# out.net
KiCad netlist of a schematic drawn in EAGLE
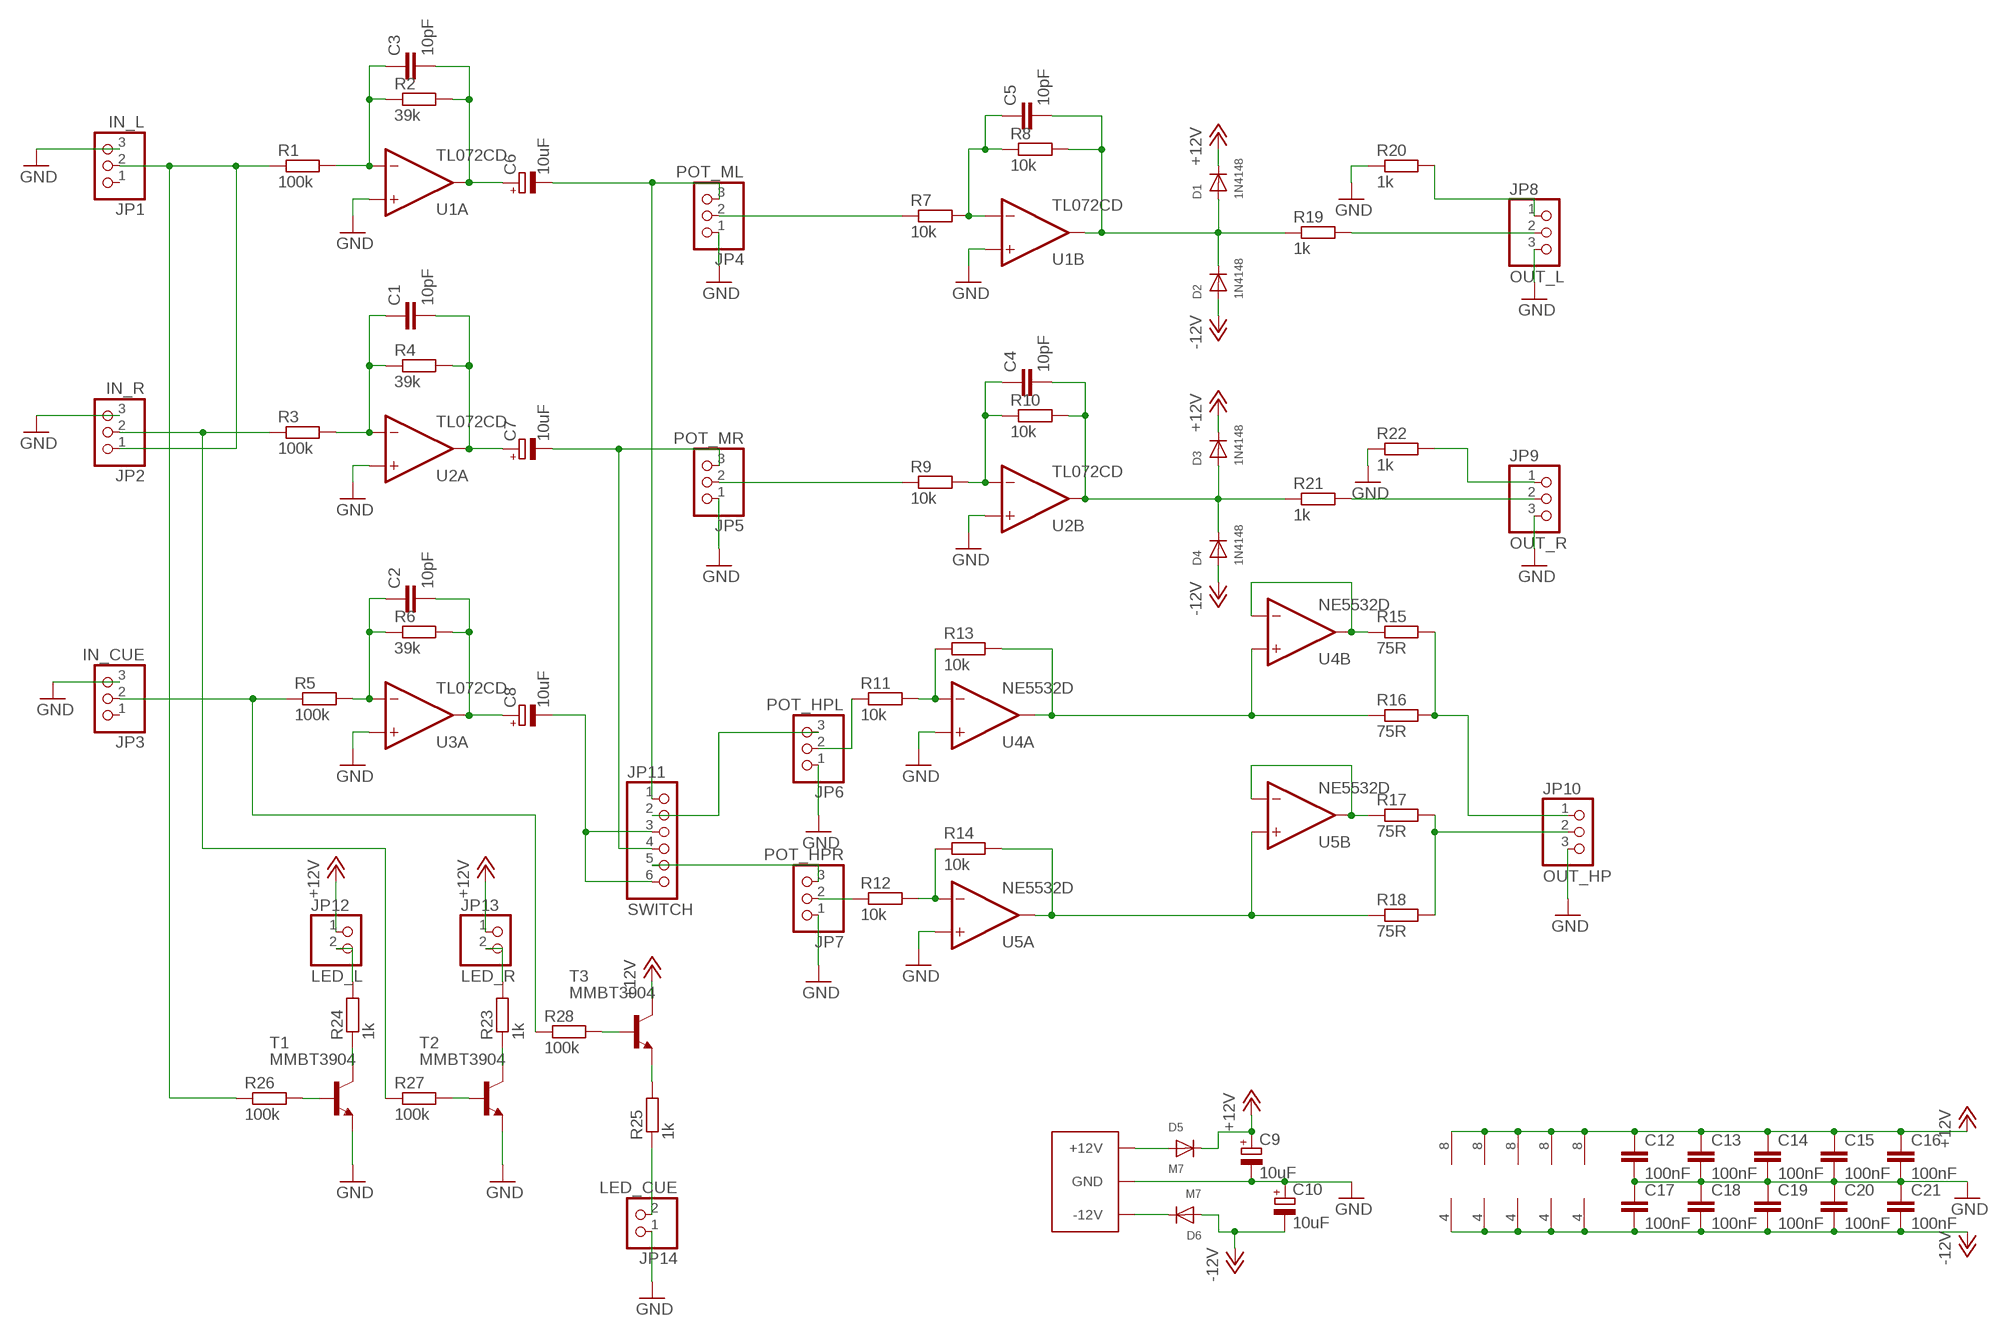
[diagram p0: schematic, sheet 1]

(export (version "E")
  (design (tool "Eeschema 10.0.6"))
  (components
    (comp (ref "C1")
      (value "10pF")
      (footprint "eagle-import:C0402")
      (libsource (lib "eagle-import") (part "C-EUC0402"))
    )
    (comp (ref "C2")
      (value "10pF")
      (footprint "eagle-import:C0402")
      (libsource (lib "eagle-import") (part "C-EUC0402"))
    )
    (comp (ref "C3")
      (value "10pF")
      (footprint "eagle-import:C0402")
      (libsource (lib "eagle-import") (part "C-EUC0402"))
    )
    (comp (ref "C4")
      (value "10pF")
      (footprint "eagle-import:C0402")
      (libsource (lib "eagle-import") (part "C-EUC0402"))
    )
    (comp (ref "C5")
      (value "10pF")
      (footprint "eagle-import:C0402")
      (libsource (lib "eagle-import") (part "C-EUC0402"))
    )
    (comp (ref "C6")
      (value "10uF")
      (footprint "eagle-import:A_3216-18W")
      (libsource (lib "eagle-import") (part "CPOL-EUA/3216-18W"))
    )
    (comp (ref "C7")
      (value "10uF")
      (footprint "eagle-import:A_3216-18W")
      (libsource (lib "eagle-import") (part "CPOL-EUA/3216-18W"))
    )
    (comp (ref "C8")
      (value "10uF")
      (footprint "eagle-import:A_3216-18W")
      (libsource (lib "eagle-import") (part "CPOL-EUA/3216-18W"))
    )
    (comp (ref "C9")
      (value "10uF")
      (footprint "eagle-import:A_3216-18W")
      (libsource (lib "eagle-import") (part "CPOL-EUA/3216-18W"))
    )
    (comp (ref "C10")
      (value "10uF")
      (footprint "eagle-import:A_3216-18W")
      (libsource (lib "eagle-import") (part "CPOL-EUA/3216-18W"))
    )
    (comp (ref "C11")
      (value "EURO_POWER_LOCKFAT-LOCK")
      (footprint "eagle-import:EURO_PWR_HEADER_LOCK")
      (libsource (lib "eagle-import") (part "EURO_POWER_LOCKFAT-LOCK"))
    )
    (comp (ref "C12")
      (value "100nF")
      (footprint "eagle-import:C0402")
      (libsource (lib "eagle-import") (part "C-EUC0402"))
    )
    (comp (ref "C13")
      (value "100nF")
      (footprint "eagle-import:C0402")
      (libsource (lib "eagle-import") (part "C-EUC0402"))
    )
    (comp (ref "C14")
      (value "100nF")
      (footprint "eagle-import:C0402")
      (libsource (lib "eagle-import") (part "C-EUC0402"))
    )
    (comp (ref "C15")
      (value "100nF")
      (footprint "eagle-import:C0402")
      (libsource (lib "eagle-import") (part "C-EUC0402"))
    )
    (comp (ref "C16")
      (value "100nF")
      (footprint "eagle-import:C0402")
      (libsource (lib "eagle-import") (part "C-EUC0402"))
    )
    (comp (ref "C17")
      (value "100nF")
      (footprint "eagle-import:C0402")
      (libsource (lib "eagle-import") (part "C-EUC0402"))
    )
    (comp (ref "C18")
      (value "100nF")
      (footprint "eagle-import:C0402")
      (libsource (lib "eagle-import") (part "C-EUC0402"))
    )
    (comp (ref "C19")
      (value "100nF")
      (footprint "eagle-import:C0402")
      (libsource (lib "eagle-import") (part "C-EUC0402"))
    )
    (comp (ref "C20")
      (value "100nF")
      (footprint "eagle-import:C0402")
      (libsource (lib "eagle-import") (part "C-EUC0402"))
    )
    (comp (ref "C21")
      (value "100nF")
      (footprint "eagle-import:C0402")
      (libsource (lib "eagle-import") (part "C-EUC0402"))
    )
    (comp (ref "D1")
      (value "1N4148")
      (footprint "eagle-import:SOD-323F")
      (libsource (lib "eagle-import") (part "DIODESOD-323F"))
    )
    (comp (ref "D2")
      (value "1N4148")
      (footprint "eagle-import:SOD-323F")
      (libsource (lib "eagle-import") (part "DIODESOD-323F"))
    )
    (comp (ref "D3")
      (value "1N4148")
      (footprint "eagle-import:SOD-323F")
      (libsource (lib "eagle-import") (part "DIODESOD-323F"))
    )
    (comp (ref "D4")
      (value "1N4148")
      (footprint "eagle-import:SOD-323F")
      (libsource (lib "eagle-import") (part "DIODESOD-323F"))
    )
    (comp (ref "D5")
      (value "M7")
      (footprint "eagle-import:SMADIODE")
      (libsource (lib "eagle-import") (part "DIODESMA"))
    )
    (comp (ref "D6")
      (value "M7")
      (footprint "eagle-import:SMADIODE")
      (libsource (lib "eagle-import") (part "DIODESMA"))
    )
    (comp (ref "JP1")
      (value "IN_L")
      (footprint "eagle-import:1X03")
      (libsource (lib "eagle-import") (part "PINHD-1X3"))
    )
    (comp (ref "JP2")
      (value "IN_R")
      (footprint "eagle-import:1X03")
      (libsource (lib "eagle-import") (part "PINHD-1X3"))
    )
    (comp (ref "JP3")
      (value "IN_CUE")
      (footprint "eagle-import:1X03")
      (libsource (lib "eagle-import") (part "PINHD-1X3"))
    )
    (comp (ref "JP4")
      (value "POT_ML")
      (footprint "eagle-import:1X03")
      (libsource (lib "eagle-import") (part "PINHD-1X3"))
    )
    (comp (ref "JP5")
      (value "POT_MR")
      (footprint "eagle-import:1X03")
      (libsource (lib "eagle-import") (part "PINHD-1X3"))
    )
    (comp (ref "JP6")
      (value "POT_HPL")
      (footprint "eagle-import:1X03")
      (libsource (lib "eagle-import") (part "PINHD-1X3"))
    )
    (comp (ref "JP7")
      (value "POT_HPR")
      (footprint "eagle-import:1X03")
      (libsource (lib "eagle-import") (part "PINHD-1X3"))
    )
    (comp (ref "JP8")
      (value "OUT_L")
      (footprint "eagle-import:1X03")
      (libsource (lib "eagle-import") (part "PINHD-1X3"))
    )
    (comp (ref "JP9")
      (value "OUT_R")
      (footprint "eagle-import:1X03")
      (libsource (lib "eagle-import") (part "PINHD-1X3"))
    )
    (comp (ref "JP10")
      (value "OUT_HP")
      (footprint "eagle-import:1X03")
      (libsource (lib "eagle-import") (part "PINHD-1X3"))
    )
    (comp (ref "JP11")
      (value "SWITCH")
      (footprint "eagle-import:1X06")
      (libsource (lib "eagle-import") (part "PINHD-1X6"))
    )
    (comp (ref "JP12")
      (value "LED_L")
      (footprint "eagle-import:1X02")
      (libsource (lib "eagle-import") (part "PINHD-1X2"))
    )
    (comp (ref "JP13")
      (value "LED_R")
      (footprint "eagle-import:1X02")
      (libsource (lib "eagle-import") (part "PINHD-1X2"))
    )
    (comp (ref "JP14")
      (value "LED_CUE")
      (footprint "eagle-import:1X02")
      (libsource (lib "eagle-import") (part "PINHD-1X2"))
    )
    (comp (ref "R1")
      (value "100k")
      (footprint "eagle-import:R0402")
      (libsource (lib "eagle-import") (part "R-EU_R0402"))
    )
    (comp (ref "R2")
      (value "39k")
      (footprint "eagle-import:R0402")
      (libsource (lib "eagle-import") (part "R-EU_R0402"))
    )
    (comp (ref "R3")
      (value "100k")
      (footprint "eagle-import:R0402")
      (libsource (lib "eagle-import") (part "R-EU_R0402"))
    )
    (comp (ref "R4")
      (value "39k")
      (footprint "eagle-import:R0402")
      (libsource (lib "eagle-import") (part "R-EU_R0402"))
    )
    (comp (ref "R5")
      (value "100k")
      (footprint "eagle-import:R0402")
      (libsource (lib "eagle-import") (part "R-EU_R0402"))
    )
    (comp (ref "R6")
      (value "39k")
      (footprint "eagle-import:R0402")
      (libsource (lib "eagle-import") (part "R-EU_R0402"))
    )
    (comp (ref "R7")
      (value "10k")
      (footprint "eagle-import:R0402")
      (libsource (lib "eagle-import") (part "R-EU_R0402"))
    )
    (comp (ref "R8")
      (value "10k")
      (footprint "eagle-import:R0402")
      (libsource (lib "eagle-import") (part "R-EU_R0402"))
    )
    (comp (ref "R9")
      (value "10k")
      (footprint "eagle-import:R0402")
      (libsource (lib "eagle-import") (part "R-EU_R0402"))
    )
    (comp (ref "R10")
      (value "10k")
      (footprint "eagle-import:R0402")
      (libsource (lib "eagle-import") (part "R-EU_R0402"))
    )
    (comp (ref "R11")
      (value "10k")
      (footprint "eagle-import:R0402")
      (libsource (lib "eagle-import") (part "R-EU_R0402"))
    )
    (comp (ref "R12")
      (value "10k")
      (footprint "eagle-import:R0402")
      (libsource (lib "eagle-import") (part "R-EU_R0402"))
    )
    (comp (ref "R13")
      (value "10k")
      (footprint "eagle-import:R0402")
      (libsource (lib "eagle-import") (part "R-EU_R0402"))
    )
    (comp (ref "R14")
      (value "10k")
      (footprint "eagle-import:R0402")
      (libsource (lib "eagle-import") (part "R-EU_R0402"))
    )
    (comp (ref "R15")
      (value "75R")
      (footprint "eagle-import:R0402")
      (libsource (lib "eagle-import") (part "R-EU_R0402"))
    )
    (comp (ref "R16")
      (value "75R")
      (footprint "eagle-import:R0402")
      (libsource (lib "eagle-import") (part "R-EU_R0402"))
    )
    (comp (ref "R17")
      (value "75R")
      (footprint "eagle-import:R0402")
      (libsource (lib "eagle-import") (part "R-EU_R0402"))
    )
    (comp (ref "R18")
      (value "75R")
      (footprint "eagle-import:R0402")
      (libsource (lib "eagle-import") (part "R-EU_R0402"))
    )
    (comp (ref "R19")
      (value "1k")
      (footprint "eagle-import:R0402")
      (libsource (lib "eagle-import") (part "R-EU_R0402"))
    )
    (comp (ref "R20")
      (value "1k")
      (footprint "eagle-import:R0402")
      (libsource (lib "eagle-import") (part "R-EU_R0402"))
    )
    (comp (ref "R21")
      (value "1k")
      (footprint "eagle-import:R0402")
      (libsource (lib "eagle-import") (part "R-EU_R0402"))
    )
    (comp (ref "R22")
      (value "1k")
      (footprint "eagle-import:R0402")
      (libsource (lib "eagle-import") (part "R-EU_R0402"))
    )
    (comp (ref "R23")
      (value "1k")
      (footprint "eagle-import:R0402")
      (libsource (lib "eagle-import") (part "R-EU_R0402"))
    )
    (comp (ref "R24")
      (value "1k")
      (footprint "eagle-import:R0402")
      (libsource (lib "eagle-import") (part "R-EU_R0402"))
    )
    (comp (ref "R25")
      (value "1k")
      (footprint "eagle-import:R0402")
      (libsource (lib "eagle-import") (part "R-EU_R0402"))
    )
    (comp (ref "R26")
      (value "100k")
      (footprint "eagle-import:R0402")
      (libsource (lib "eagle-import") (part "R-EU_R0402"))
    )
    (comp (ref "R27")
      (value "100k")
      (footprint "eagle-import:R0402")
      (libsource (lib "eagle-import") (part "R-EU_R0402"))
    )
    (comp (ref "R28")
      (value "100k")
      (footprint "eagle-import:R0402")
      (libsource (lib "eagle-import") (part "R-EU_R0402"))
    )
    (comp (ref "T1")
      (value "MMBT3904")
      (footprint "eagle-import:SOT23-BEC")
      (libsource (lib "eagle-import") (part "-NPN-SOT23-BECMMBT3904LT1"))
    )
    (comp (ref "T2")
      (value "MMBT3904")
      (footprint "eagle-import:SOT23-BEC")
      (libsource (lib "eagle-import") (part "-NPN-SOT23-BECMMBT3904LT1"))
    )
    (comp (ref "T3")
      (value "MMBT3904")
      (footprint "eagle-import:SOT23-BEC")
      (libsource (lib "eagle-import") (part "-NPN-SOT23-BECMMBT3904LT1"))
    )
    (comp (ref "U1")
      (value "TL072CD")
      (footprint "eagle-import:SOIC8")
      (libsource (lib "eagle-import") (part "TL072DC"))
    )
    (comp (ref "U2")
      (value "TL072CD")
      (footprint "eagle-import:SOIC8")
      (libsource (lib "eagle-import") (part "TL072DC"))
    )
    (comp (ref "U3")
      (value "TL072CD")
      (footprint "eagle-import:SOIC8")
      (libsource (lib "eagle-import") (part "TL072DC"))
    )
    (comp (ref "U4")
      (value "NE5532D")
      (footprint "eagle-import:SOIC8")
      (libsource (lib "eagle-import") (part "NE5532D"))
    )
    (comp (ref "U5")
      (value "NE5532D")
      (footprint "eagle-import:SOIC8")
      (libsource (lib "eagle-import") (part "NE5532D"))
    )
  )
  (nets
    (net (code "1") (name "+12V") (class "Default")
      (node (ref "C12") (pin "1") (pinfunction "1_1") (pintype "passive"))
      (node (ref "C13") (pin "1") (pinfunction "1_1") (pintype "passive"))
      (node (ref "C14") (pin "1") (pinfunction "1_1") (pintype "passive"))
      (node (ref "C15") (pin "1") (pinfunction "1_1") (pintype "passive"))
      (node (ref "C16") (pin "1") (pinfunction "1_1") (pintype "passive"))
      (node (ref "C9") (pin "+") (pinfunction "+_+") (pintype "passive"))
      (node (ref "D1") (pin "C") (pinfunction "C_C") (pintype "passive"))
      (node (ref "D3") (pin "C") (pinfunction "C_C") (pintype "passive"))
      (node (ref "D5") (pin "C") (pinfunction "C_C") (pintype "passive"))
      (node (ref "JP12") (pin "1") (pinfunction "1_1") (pintype "passive"))
      (node (ref "JP13") (pin "1") (pinfunction "1_1") (pintype "passive"))
      (node (ref "T3") (pin "C") (pinfunction "C_C") (pintype "passive"))
      (node (ref "U1") (pin "8") (pinfunction "V+_8") (pintype "power_in"))
      (node (ref "U2") (pin "8") (pinfunction "V+_8") (pintype "power_in"))
      (node (ref "U3") (pin "8") (pinfunction "V+_8") (pintype "power_in"))
      (node (ref "U4") (pin "8") (pinfunction "V+_8") (pintype "power_in"))
      (node (ref "U5") (pin "8") (pinfunction "V+_8") (pintype "power_in"))
    )
    (net (code "2") (name "-12V") (class "Default")
      (node (ref "C10") (pin "-") (pinfunction "-_-") (pintype "passive"))
      (node (ref "C17") (pin "2") (pinfunction "2_2") (pintype "passive"))
      (node (ref "C18") (pin "2") (pinfunction "2_2") (pintype "passive"))
      (node (ref "C19") (pin "2") (pinfunction "2_2") (pintype "passive"))
      (node (ref "C20") (pin "2") (pinfunction "2_2") (pintype "passive"))
      (node (ref "C21") (pin "2") (pinfunction "2_2") (pintype "passive"))
      (node (ref "D2") (pin "A") (pinfunction "A_A") (pintype "passive"))
      (node (ref "D4") (pin "A") (pinfunction "A_A") (pintype "passive"))
      (node (ref "D6") (pin "A") (pinfunction "A_A") (pintype "passive"))
      (node (ref "U1") (pin "4") (pinfunction "V-_4") (pintype "power_in"))
      (node (ref "U2") (pin "4") (pinfunction "V-_4") (pintype "power_in"))
      (node (ref "U3") (pin "4") (pinfunction "V-_4") (pintype "power_in"))
      (node (ref "U4") (pin "4") (pinfunction "V-_4") (pintype "power_in"))
      (node (ref "U5") (pin "4") (pinfunction "V-_4") (pintype "power_in"))
    )
    (net (code "3") (name "GND") (class "Default")
      (node (ref "C10") (pin "+") (pinfunction "+_+") (pintype "passive"))
      (node (ref "C11") (pin "GND1") (pinfunction "GND_GND1") (pintype "bidirectional"))
      (node (ref "C11") (pin "GND2") (pinfunction "GND_GND2") (pintype "bidirectional"))
      (node (ref "C11") (pin "GND3") (pinfunction "GND_GND3") (pintype "bidirectional"))
      (node (ref "C11") (pin "GND4") (pinfunction "GND_GND4") (pintype "bidirectional"))
      (node (ref "C11") (pin "GND5") (pinfunction "GND_GND5") (pintype "bidirectional"))
      (node (ref "C11") (pin "GND6") (pinfunction "GND_GND6") (pintype "bidirectional"))
      (node (ref "C12") (pin "2") (pinfunction "2_2") (pintype "passive"))
      (node (ref "C13") (pin "2") (pinfunction "2_2") (pintype "passive"))
      (node (ref "C14") (pin "2") (pinfunction "2_2") (pintype "passive"))
      (node (ref "C15") (pin "2") (pinfunction "2_2") (pintype "passive"))
      (node (ref "C16") (pin "2") (pinfunction "2_2") (pintype "passive"))
      (node (ref "C17") (pin "1") (pinfunction "1_1") (pintype "passive"))
      (node (ref "C18") (pin "1") (pinfunction "1_1") (pintype "passive"))
      (node (ref "C19") (pin "1") (pinfunction "1_1") (pintype "passive"))
      (node (ref "C20") (pin "1") (pinfunction "1_1") (pintype "passive"))
      (node (ref "C21") (pin "1") (pinfunction "1_1") (pintype "passive"))
      (node (ref "C9") (pin "-") (pinfunction "-_-") (pintype "passive"))
      (node (ref "JP1") (pin "3") (pinfunction "3_3") (pintype "passive"))
      (node (ref "JP10") (pin "3") (pinfunction "3_3") (pintype "passive"))
      (node (ref "JP14") (pin "1") (pinfunction "1_1") (pintype "passive"))
      (node (ref "JP2") (pin "3") (pinfunction "3_3") (pintype "passive"))
      (node (ref "JP3") (pin "3") (pinfunction "3_3") (pintype "passive"))
      (node (ref "JP4") (pin "1") (pinfunction "1_1") (pintype "passive"))
      (node (ref "JP5") (pin "1") (pinfunction "1_1") (pintype "passive"))
      (node (ref "JP6") (pin "1") (pinfunction "1_1") (pintype "passive"))
      (node (ref "JP7") (pin "1") (pinfunction "1_1") (pintype "passive"))
      (node (ref "JP8") (pin "3") (pinfunction "3_3") (pintype "passive"))
      (node (ref "JP9") (pin "3") (pinfunction "3_3") (pintype "passive"))
      (node (ref "R20") (pin "1") (pinfunction "1_1") (pintype "passive"))
      (node (ref "R22") (pin "1") (pinfunction "1_1") (pintype "passive"))
      (node (ref "T1") (pin "E") (pinfunction "E_E") (pintype "passive"))
      (node (ref "T2") (pin "E") (pinfunction "E_E") (pintype "passive"))
      (node (ref "U1") (pin "3") (pinfunction "+IN_3") (pintype "input"))
      (node (ref "U1") (pin "5") (pinfunction "+IN_5") (pintype "input"))
      (node (ref "U2") (pin "3") (pinfunction "+IN_3") (pintype "input"))
      (node (ref "U2") (pin "5") (pinfunction "+IN_5") (pintype "input"))
      (node (ref "U3") (pin "3") (pinfunction "+IN_3") (pintype "input"))
      (node (ref "U4") (pin "3") (pinfunction "+IN_3") (pintype "input"))
      (node (ref "U5") (pin "3") (pinfunction "+IN_3") (pintype "input"))
    )
    (net (code "4") (name "Net-(C6-Pad-)") (class "Default")
      (node (ref "C6") (pin "-") (pinfunction "-_-") (pintype "passive"))
      (node (ref "JP11") (pin "1") (pinfunction "1_1") (pintype "passive"))
      (node (ref "JP4") (pin "3") (pinfunction "3_3") (pintype "passive"))
    )
    (net (code "5") (name "Net-(C7-Pad-)") (class "Default")
      (node (ref "C7") (pin "-") (pinfunction "-_-") (pintype "passive"))
      (node (ref "JP11") (pin "4") (pinfunction "4_4") (pintype "passive"))
      (node (ref "JP5") (pin "3") (pinfunction "3_3") (pintype "passive"))
    )
    (net (code "6") (name "Net-(C8-Pad-)") (class "Default")
      (node (ref "C8") (pin "-") (pinfunction "-_-") (pintype "passive"))
      (node (ref "JP11") (pin "3") (pinfunction "3_3") (pintype "passive"))
      (node (ref "JP11") (pin "6") (pinfunction "6_6") (pintype "passive"))
    )
    (net (code "7") (name "Net-(C11-+12V-PadPOS1)") (class "Default")
      (node (ref "C11") (pin "POS1") (pinfunction "+12V_POS1") (pintype "bidirectional"))
      (node (ref "C11") (pin "POS2") (pinfunction "+12V_POS2") (pintype "bidirectional"))
      (node (ref "D5") (pin "A") (pinfunction "A_A") (pintype "passive"))
    )
    (net (code "8") (name "Net-(C11--12V-PadNEG1)") (class "Default")
      (node (ref "C11") (pin "NEG1") (pinfunction "-12V_NEG1") (pintype "bidirectional"))
      (node (ref "C11") (pin "NEG2") (pinfunction "-12V_NEG2") (pintype "bidirectional"))
      (node (ref "D6") (pin "C") (pinfunction "C_C") (pintype "passive"))
    )
    (net (code "9") (name "Net-(JP1-Pad2)") (class "Default")
      (node (ref "JP1") (pin "2") (pinfunction "2_2") (pintype "passive"))
      (node (ref "JP2") (pin "1") (pinfunction "1_1") (pintype "passive"))
      (node (ref "R1") (pin "1") (pinfunction "1_1") (pintype "passive"))
      (node (ref "R26") (pin "1") (pinfunction "1_1") (pintype "passive"))
    )
    (net (code "10") (name "Net-(JP2-Pad2)") (class "Default")
      (node (ref "JP2") (pin "2") (pinfunction "2_2") (pintype "passive"))
      (node (ref "R27") (pin "1") (pinfunction "1_1") (pintype "passive"))
      (node (ref "R3") (pin "1") (pinfunction "1_1") (pintype "passive"))
    )
    (net (code "11") (name "Net-(JP3-Pad2)") (class "Default")
      (node (ref "JP3") (pin "2") (pinfunction "2_2") (pintype "passive"))
      (node (ref "R28") (pin "1") (pinfunction "1_1") (pintype "passive"))
      (node (ref "R5") (pin "1") (pinfunction "1_1") (pintype "passive"))
    )
    (net (code "12") (name "Net-(JP4-Pad2)") (class "Default")
      (node (ref "JP4") (pin "2") (pinfunction "2_2") (pintype "passive"))
      (node (ref "R7") (pin "1") (pinfunction "1_1") (pintype "passive"))
    )
    (net (code "13") (name "Net-(JP5-Pad2)") (class "Default")
      (node (ref "JP5") (pin "2") (pinfunction "2_2") (pintype "passive"))
      (node (ref "R9") (pin "1") (pinfunction "1_1") (pintype "passive"))
    )
    (net (code "14") (name "Net-(JP6-Pad2)") (class "Default")
      (node (ref "JP6") (pin "2") (pinfunction "2_2") (pintype "passive"))
      (node (ref "R11") (pin "1") (pinfunction "1_1") (pintype "passive"))
    )
    (net (code "15") (name "Net-(JP7-Pad2)") (class "Default")
      (node (ref "JP7") (pin "2") (pinfunction "2_2") (pintype "passive"))
      (node (ref "R12") (pin "1") (pinfunction "1_1") (pintype "passive"))
    )
    (net (code "16") (name "Net-(JP8-Pad1)") (class "Default")
      (node (ref "JP8") (pin "1") (pinfunction "1_1") (pintype "passive"))
      (node (ref "R20") (pin "2") (pinfunction "2_2") (pintype "passive"))
    )
    (net (code "17") (name "Net-(JP8-Pad2)") (class "Default")
      (node (ref "JP8") (pin "2") (pinfunction "2_2") (pintype "passive"))
      (node (ref "R19") (pin "2") (pinfunction "2_2") (pintype "passive"))
    )
    (net (code "18") (name "Net-(JP9-Pad1)") (class "Default")
      (node (ref "JP9") (pin "1") (pinfunction "1_1") (pintype "passive"))
      (node (ref "R22") (pin "2") (pinfunction "2_2") (pintype "passive"))
    )
    (net (code "19") (name "Net-(JP9-Pad2)") (class "Default")
      (node (ref "JP9") (pin "2") (pinfunction "2_2") (pintype "passive"))
      (node (ref "R21") (pin "2") (pinfunction "2_2") (pintype "passive"))
    )
    (net (code "20") (name "Net-(JP10-Pad1)") (class "Default")
      (node (ref "JP10") (pin "1") (pinfunction "1_1") (pintype "passive"))
      (node (ref "R15") (pin "2") (pinfunction "2_2") (pintype "passive"))
      (node (ref "R16") (pin "2") (pinfunction "2_2") (pintype "passive"))
    )
    (net (code "21") (name "Net-(JP10-Pad2)") (class "Default")
      (node (ref "JP10") (pin "2") (pinfunction "2_2") (pintype "passive"))
      (node (ref "R17") (pin "2") (pinfunction "2_2") (pintype "passive"))
      (node (ref "R18") (pin "2") (pinfunction "2_2") (pintype "passive"))
    )
    (net (code "22") (name "Net-(JP11-Pad2)") (class "Default")
      (node (ref "JP11") (pin "2") (pinfunction "2_2") (pintype "passive"))
      (node (ref "JP6") (pin "3") (pinfunction "3_3") (pintype "passive"))
    )
    (net (code "23") (name "Net-(JP11-Pad5)") (class "Default")
      (node (ref "JP11") (pin "5") (pinfunction "5_5") (pintype "passive"))
      (node (ref "JP7") (pin "3") (pinfunction "3_3") (pintype "passive"))
    )
    (net (code "24") (name "Net-(JP12-Pad2)") (class "Default")
      (node (ref "JP12") (pin "2") (pinfunction "2_2") (pintype "passive"))
      (node (ref "R24") (pin "2") (pinfunction "2_2") (pintype "passive"))
    )
    (net (code "25") (name "Net-(JP13-Pad2)") (class "Default")
      (node (ref "JP13") (pin "2") (pinfunction "2_2") (pintype "passive"))
      (node (ref "R23") (pin "2") (pinfunction "2_2") (pintype "passive"))
    )
    (net (code "26") (name "Net-(JP14-Pad2)") (class "Default")
      (node (ref "JP14") (pin "2") (pinfunction "2_2") (pintype "passive"))
      (node (ref "R25") (pin "1") (pinfunction "1_1") (pintype "passive"))
    )
    (net (code "27") (name "Net-(R23-Pad1)") (class "Default")
      (node (ref "R23") (pin "1") (pinfunction "1_1") (pintype "passive"))
      (node (ref "T2") (pin "C") (pinfunction "C_C") (pintype "passive"))
    )
    (net (code "28") (name "Net-(R24-Pad1)") (class "Default")
      (node (ref "R24") (pin "1") (pinfunction "1_1") (pintype "passive"))
      (node (ref "T1") (pin "C") (pinfunction "C_C") (pintype "passive"))
    )
    (net (code "29") (name "Net-(R25-Pad2)") (class "Default")
      (node (ref "R25") (pin "2") (pinfunction "2_2") (pintype "passive"))
      (node (ref "T3") (pin "E") (pinfunction "E_E") (pintype "passive"))
    )
    (net (code "30") (name "Net-(R26-Pad2)") (class "Default")
      (node (ref "R26") (pin "2") (pinfunction "2_2") (pintype "passive"))
      (node (ref "T1") (pin "B") (pinfunction "B_B") (pintype "passive"))
    )
    (net (code "31") (name "Net-(R27-Pad2)") (class "Default")
      (node (ref "R27") (pin "2") (pinfunction "2_2") (pintype "passive"))
      (node (ref "T2") (pin "B") (pinfunction "B_B") (pintype "passive"))
    )
    (net (code "32") (name "Net-(R28-Pad2)") (class "Default")
      (node (ref "R28") (pin "2") (pinfunction "2_2") (pintype "passive"))
      (node (ref "T3") (pin "B") (pinfunction "B_B") (pintype "passive"))
    )
    (net (code "33") (name "Net-(U1A--IN)") (class "Default")
      (node (ref "C3") (pin "1") (pinfunction "1_1") (pintype "passive"))
      (node (ref "R1") (pin "2") (pinfunction "2_2") (pintype "passive"))
      (node (ref "R2") (pin "1") (pinfunction "1_1") (pintype "passive"))
      (node (ref "U1") (pin "2") (pinfunction "-IN_2") (pintype "input"))
    )
    (net (code "34") (name "Net-(U1A-OUT)") (class "Default")
      (node (ref "C3") (pin "2") (pinfunction "2_2") (pintype "passive"))
      (node (ref "C6") (pin "+") (pinfunction "+_+") (pintype "passive"))
      (node (ref "R2") (pin "2") (pinfunction "2_2") (pintype "passive"))
      (node (ref "U1") (pin "1") (pinfunction "OUT_1") (pintype "output"))
    )
    (net (code "35") (name "Net-(U1B--IN)") (class "Default")
      (node (ref "C5") (pin "1") (pinfunction "1_1") (pintype "passive"))
      (node (ref "R7") (pin "2") (pinfunction "2_2") (pintype "passive"))
      (node (ref "R8") (pin "1") (pinfunction "1_1") (pintype "passive"))
      (node (ref "U1") (pin "6") (pinfunction "-IN_6") (pintype "input"))
    )
    (net (code "36") (name "Net-(U1B-OUT)") (class "Default")
      (node (ref "C5") (pin "2") (pinfunction "2_2") (pintype "passive"))
      (node (ref "D1") (pin "A") (pinfunction "A_A") (pintype "passive"))
      (node (ref "D2") (pin "C") (pinfunction "C_C") (pintype "passive"))
      (node (ref "R19") (pin "1") (pinfunction "1_1") (pintype "passive"))
      (node (ref "R8") (pin "2") (pinfunction "2_2") (pintype "passive"))
      (node (ref "U1") (pin "7") (pinfunction "OUT_7") (pintype "output"))
    )
    (net (code "37") (name "Net-(U2A--IN)") (class "Default")
      (node (ref "C1") (pin "1") (pinfunction "1_1") (pintype "passive"))
      (node (ref "R3") (pin "2") (pinfunction "2_2") (pintype "passive"))
      (node (ref "R4") (pin "1") (pinfunction "1_1") (pintype "passive"))
      (node (ref "U2") (pin "2") (pinfunction "-IN_2") (pintype "input"))
    )
    (net (code "38") (name "Net-(U2A-OUT)") (class "Default")
      (node (ref "C1") (pin "2") (pinfunction "2_2") (pintype "passive"))
      (node (ref "C7") (pin "+") (pinfunction "+_+") (pintype "passive"))
      (node (ref "R4") (pin "2") (pinfunction "2_2") (pintype "passive"))
      (node (ref "U2") (pin "1") (pinfunction "OUT_1") (pintype "output"))
    )
    (net (code "39") (name "Net-(U2B--IN)") (class "Default")
      (node (ref "C4") (pin "1") (pinfunction "1_1") (pintype "passive"))
      (node (ref "R10") (pin "1") (pinfunction "1_1") (pintype "passive"))
      (node (ref "R9") (pin "2") (pinfunction "2_2") (pintype "passive"))
      (node (ref "U2") (pin "6") (pinfunction "-IN_6") (pintype "input"))
    )
    (net (code "40") (name "Net-(U2B-OUT)") (class "Default")
      (node (ref "C4") (pin "2") (pinfunction "2_2") (pintype "passive"))
      (node (ref "D3") (pin "A") (pinfunction "A_A") (pintype "passive"))
      (node (ref "D4") (pin "C") (pinfunction "C_C") (pintype "passive"))
      (node (ref "R10") (pin "2") (pinfunction "2_2") (pintype "passive"))
      (node (ref "R21") (pin "1") (pinfunction "1_1") (pintype "passive"))
      (node (ref "U2") (pin "7") (pinfunction "OUT_7") (pintype "output"))
    )
    (net (code "41") (name "Net-(U3A--IN)") (class "Default")
      (node (ref "C2") (pin "1") (pinfunction "1_1") (pintype "passive"))
      (node (ref "R5") (pin "2") (pinfunction "2_2") (pintype "passive"))
      (node (ref "R6") (pin "1") (pinfunction "1_1") (pintype "passive"))
      (node (ref "U3") (pin "2") (pinfunction "-IN_2") (pintype "input"))
    )
    (net (code "42") (name "Net-(U3A-OUT)") (class "Default")
      (node (ref "C2") (pin "2") (pinfunction "2_2") (pintype "passive"))
      (node (ref "C8") (pin "+") (pinfunction "+_+") (pintype "passive"))
      (node (ref "R6") (pin "2") (pinfunction "2_2") (pintype "passive"))
      (node (ref "U3") (pin "1") (pinfunction "OUT_1") (pintype "output"))
    )
    (net (code "43") (name "Net-(U4A--IN)") (class "Default")
      (node (ref "R11") (pin "2") (pinfunction "2_2") (pintype "passive"))
      (node (ref "R13") (pin "1") (pinfunction "1_1") (pintype "passive"))
      (node (ref "U4") (pin "2") (pinfunction "-IN_2") (pintype "input"))
    )
    (net (code "44") (name "Net-(U4A-OUT)") (class "Default")
      (node (ref "R13") (pin "2") (pinfunction "2_2") (pintype "passive"))
      (node (ref "R16") (pin "1") (pinfunction "1_1") (pintype "passive"))
      (node (ref "U4") (pin "1") (pinfunction "OUT_1") (pintype "output"))
      (node (ref "U4") (pin "5") (pinfunction "+IN_5") (pintype "input"))
    )
    (net (code "45") (name "Net-(U4B--IN)") (class "Default")
      (node (ref "R15") (pin "1") (pinfunction "1_1") (pintype "passive"))
      (node (ref "U4") (pin "6") (pinfunction "-IN_6") (pintype "input"))
      (node (ref "U4") (pin "7") (pinfunction "OUT_7") (pintype "output"))
    )
    (net (code "46") (name "Net-(U5A--IN)") (class "Default")
      (node (ref "R12") (pin "2") (pinfunction "2_2") (pintype "passive"))
      (node (ref "R14") (pin "1") (pinfunction "1_1") (pintype "passive"))
      (node (ref "U5") (pin "2") (pinfunction "-IN_2") (pintype "input"))
    )
    (net (code "47") (name "Net-(U5A-OUT)") (class "Default")
      (node (ref "R14") (pin "2") (pinfunction "2_2") (pintype "passive"))
      (node (ref "R18") (pin "1") (pinfunction "1_1") (pintype "passive"))
      (node (ref "U5") (pin "1") (pinfunction "OUT_1") (pintype "output"))
      (node (ref "U5") (pin "5") (pinfunction "+IN_5") (pintype "input"))
    )
    (net (code "48") (name "Net-(U5B--IN)") (class "Default")
      (node (ref "R17") (pin "1") (pinfunction "1_1") (pintype "passive"))
      (node (ref "U5") (pin "6") (pinfunction "-IN_6") (pintype "input"))
      (node (ref "U5") (pin "7") (pinfunction "OUT_7") (pintype "output"))
    )
    (net (code "49") (name "unconnected-(JP1-Pad1)") (class "Default")
      (node (ref "JP1") (pin "1") (pinfunction "1_1") (pintype "passive"))
    )
    (net (code "50") (name "unconnected-(JP3-Pad1)") (class "Default")
      (node (ref "JP3") (pin "1") (pinfunction "1_1") (pintype "passive"))
    )
  )
)
